# WL-FRONT.net
KiCad netlist of a schematic drawn in Altium Designer
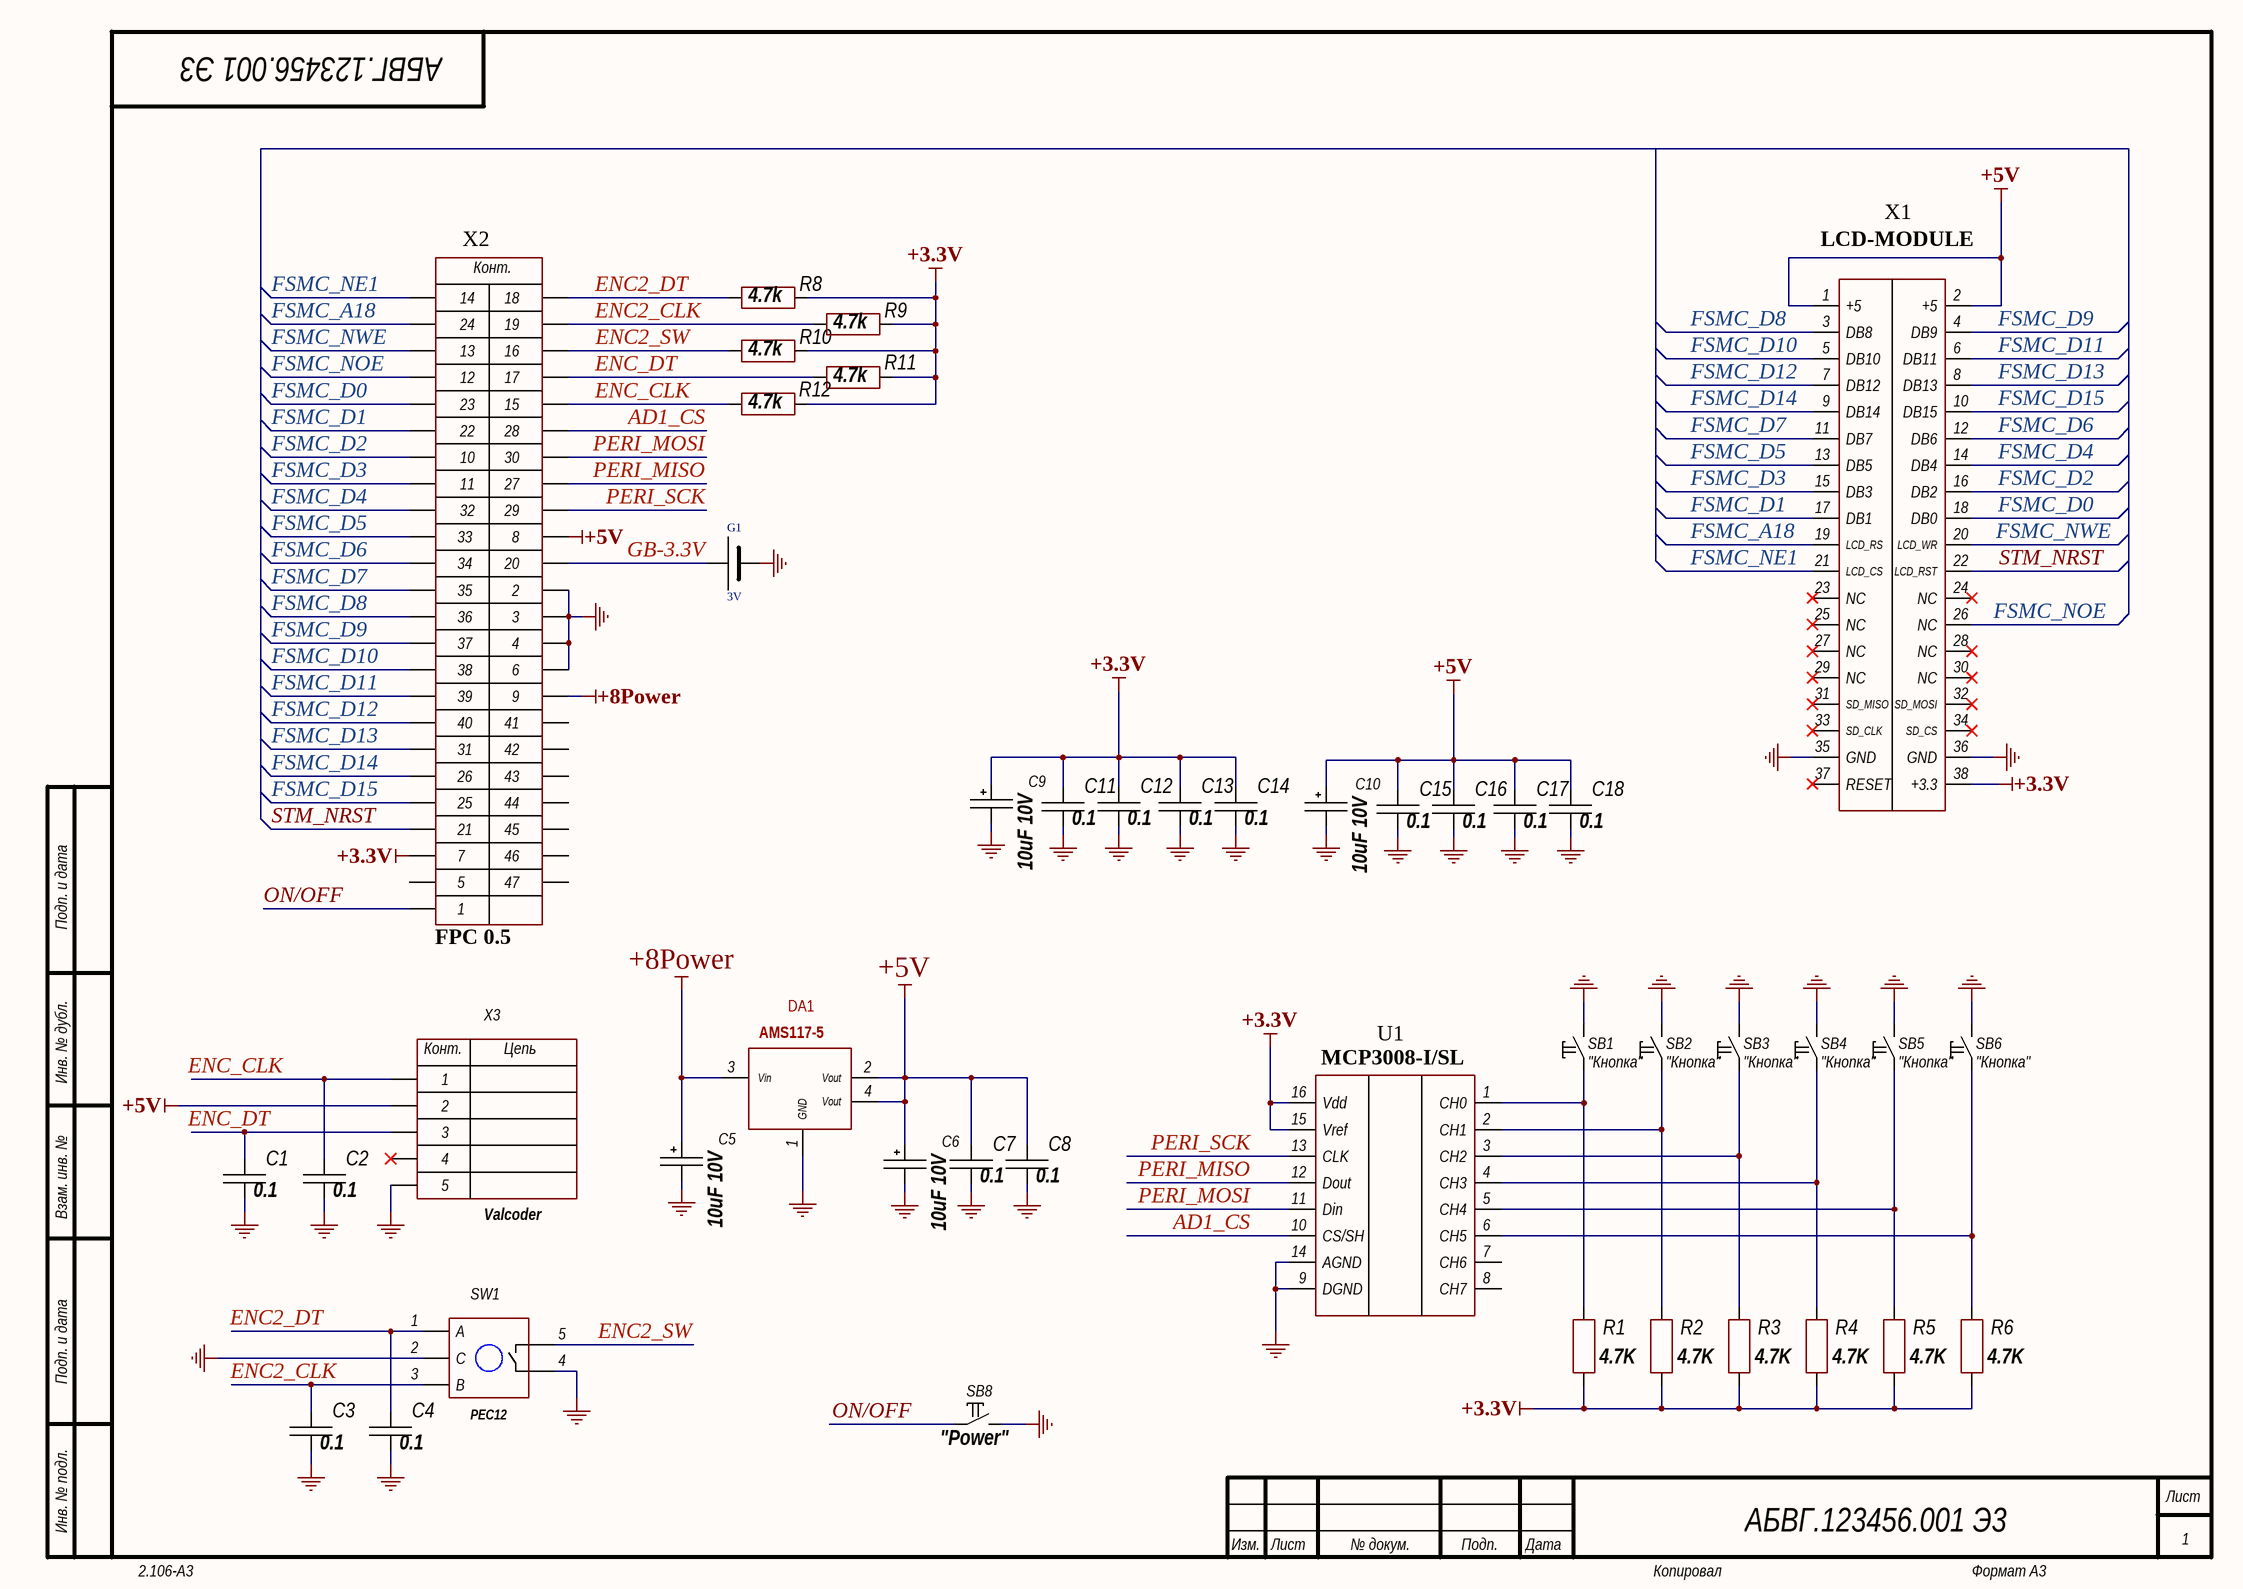
[diagram p0: WL-FRONT.SchDoc]

(export (version "E")
  (design (tool "Eeschema 10.0.6"))
  (components
    (comp (ref "C1")
      (value "0.1")
      (footprint "standard:CH0805C")
      (libsource (lib "Discrete") (part "Capacitor"))
    )
    (comp (ref "C2")
      (value "0.1")
      (footprint "standard:CH0805C")
      (libsource (lib "Discrete") (part "Capacitor"))
    )
    (comp (ref "C3")
      (value "0.1")
      (footprint "standard:CH0805C")
      (libsource (lib "Discrete") (part "Capacitor"))
    )
    (comp (ref "C4")
      (value "0.1")
      (footprint "standard:CH0805C")
      (libsource (lib "Discrete") (part "Capacitor"))
    )
    (comp (ref "C5")
      (value "10uF 10V")
      (footprint "standard:TANTAL_B")
      (libsource (lib "Discrete") (part "TantalCap"))
    )
    (comp (ref "C6")
      (value "10uF 10V")
      (footprint "standard:TANTAL_B")
      (libsource (lib "Discrete") (part "TantalCap"))
    )
    (comp (ref "C7")
      (value "0.1")
      (footprint "standard:CH0805C")
      (libsource (lib "Discrete") (part "Capacitor"))
    )
    (comp (ref "C8")
      (value "0.1")
      (footprint "standard:CH0805C")
      (libsource (lib "Discrete") (part "Capacitor"))
    )
    (comp (ref "C9")
      (value "10uF 10V")
      (footprint "standard:TANTAL_B")
      (libsource (lib "Discrete") (part "TantalCap"))
    )
    (comp (ref "C10")
      (value "10uF 10V")
      (footprint "standard:TANTAL_B")
      (libsource (lib "Discrete") (part "TantalCap"))
    )
    (comp (ref "C11")
      (value "0.1")
      (footprint "standard:CH0805C")
      (libsource (lib "Discrete") (part "Capacitor"))
    )
    (comp (ref "C12")
      (value "0.1")
      (footprint "standard:CH0805C")
      (libsource (lib "Discrete") (part "Capacitor"))
    )
    (comp (ref "C13")
      (value "0.1")
      (footprint "standard:CH0805C")
      (libsource (lib "Discrete") (part "Capacitor"))
    )
    (comp (ref "C14")
      (value "0.1")
      (footprint "standard:CH0805C")
      (libsource (lib "Discrete") (part "Capacitor"))
    )
    (comp (ref "C15")
      (value "0.1")
      (footprint "standard:CH0805C")
      (libsource (lib "Discrete") (part "Capacitor"))
    )
    (comp (ref "C16")
      (value "0.1")
      (footprint "standard:CH0805C")
      (libsource (lib "Discrete") (part "Capacitor"))
    )
    (comp (ref "C17")
      (value "0.1")
      (footprint "standard:CH0805C")
      (libsource (lib "Discrete") (part "Capacitor"))
    )
    (comp (ref "C18")
      (value "0.1")
      (footprint "standard:CH0805C")
      (libsource (lib "Discrete") (part "Capacitor"))
    )
    (comp (ref "DA1") (value "AMS117-5") (footprint "SOT223") (libsource (lib "Analog") (part "AMS117")))
    (comp (ref "G1")
      (value "3V")
      (footprint "BAT: CH224-2032")
      (libsource (lib "Connectors") (part "POWER_BAT"))
    )
    (comp (ref "R1") (value "4.7K") (footprint "standard:CH0805R") (libsource (lib "") (part "Resistor_1")))
    (comp (ref "R2") (value "4.7K") (footprint "standard:CH0805R") (libsource (lib "") (part "Resistor_1")))
    (comp (ref "R3") (value "4.7K") (footprint "standard:CH0805R") (libsource (lib "") (part "Resistor_2")))
    (comp (ref "R4") (value "4.7K") (footprint "standard:CH0805R") (libsource (lib "") (part "Resistor_1")))
    (comp (ref "R5") (value "4.7K") (footprint "standard:CH0805R") (libsource (lib "") (part "Resistor_1")))
    (comp (ref "R6") (value "4.7K") (footprint "standard:CH0805R") (libsource (lib "") (part "Resistor_1")))
    (comp (ref "R8")
      (value "4.7k")
      (footprint "standard:CH0805R")
      (libsource (lib "Discrete") (part "Resistor"))
    )
    (comp (ref "R9")
      (value "4.7k")
      (footprint "standard:CH0805R")
      (libsource (lib "Discrete") (part "Resistor"))
    )
    (comp (ref "R10")
      (value "4.7k")
      (footprint "standard:CH0805R")
      (libsource (lib "Discrete") (part "Resistor"))
    )
    (comp (ref "R11")
      (value "4.7k")
      (footprint "standard:CH0805R")
      (libsource (lib "Discrete") (part "Resistor"))
    )
    (comp (ref "R12")
      (value "4.7k")
      (footprint "standard:CH0805R")
      (libsource (lib "Discrete") (part "Resistor"))
    )
    (comp (ref "SB1")
      (value "\"Кнопка\"")
      (footprint "custom:BUT: 6x6 SMD")
      (description "6x6 mm")
      (libsource (lib "Connectors") (part "Tactile switches"))
    )
    (comp (ref "SB2")
      (value "\"Кнопка\"")
      (footprint "custom:BUT: 6x6 SMD")
      (description "6x6 mm")
      (libsource (lib "Connectors") (part "Tactile switches"))
    )
    (comp (ref "SB3")
      (value "\"Кнопка\"")
      (footprint "custom:BUT: 6x6 SMD")
      (description "6x6 mm")
      (libsource (lib "") (part "Tactile switches_1"))
    )
    (comp (ref "SB4")
      (value "\"Кнопка\"")
      (footprint "custom:BUT: 6x6 SMD")
      (description "6x6 mm")
      (libsource (lib "Connectors") (part "Tactile switches"))
    )
    (comp (ref "SB5")
      (value "\"Кнопка\"")
      (footprint "custom:BUT: 6x6 SMD")
      (description "6x6 mm")
      (libsource (lib "Connectors") (part "Tactile switches"))
    )
    (comp (ref "SB6")
      (value "\"Кнопка\"")
      (footprint "custom:BUT: 6x6 SMD")
      (description "6x6 mm")
      (libsource (lib "Connectors") (part "Tactile switches"))
    )
    (comp (ref "SB8")
      (value "\"Power\"")
      (footprint "custom:BUT: 6x6")
      (description "6x6 mm")
      (libsource (lib "Connectors") (part "Tactile switches"))
    )
    (comp (ref "SW1")
      (value "PEC12")
      (footprint "Valkoder-m2")
      (description "Encoder")
      (libsource (lib "Connectors") (part "PEC12"))
    )
    (comp (ref "U1")
      (value "MCP3008-I/SL")
      (footprint "16-SOIC")
      (libsource (lib "Digital") (part "MCP3008-I/SL"))
    )
    (comp (ref "X1")
      (value "LCD-MODULE")
      (footprint "TFT3.2-320x480-pin")
      (libsource (lib "Digital") (part "LCD-MODULE"))
    )
    (comp (ref "X2")
      (value "FPC 0.5")
      (footprint "CON: PBD2x20")
      (libsource (lib "Connectors") (part "FPC-45-0.5"))
    )
    (comp (ref "X3")
      (value "Valcoder")
      (footprint "custom:CON: PLS-5")
      (libsource (lib "Connectors") (part "5-Connector"))
    )
  )
  (nets
    (net (code "1") (name "+3.3V") (class "Default")
      (node (ref "C11") (pin "1") (pinfunction "1_1") (pintype "power_in"))
      (node (ref "C12") (pin "1") (pinfunction "1_1") (pintype "power_in"))
      (node (ref "C13") (pin "1") (pinfunction "1_1") (pintype "power_in"))
      (node (ref "C14") (pin "1") (pinfunction "1_1") (pintype "power_in"))
      (node (ref "C9") (pin "1") (pinfunction "1_1") (pintype "power_in"))
      (node (ref "R1") (pin "1") (pinfunction "1_1") (pintype "passive"))
      (node (ref "R10") (pin "1") (pinfunction "1_1") (pintype "passive"))
      (node (ref "R11") (pin "1") (pinfunction "1_1") (pintype "passive"))
      (node (ref "R12") (pin "1") (pinfunction "1_1") (pintype "passive"))
      (node (ref "R2") (pin "1") (pinfunction "1_1") (pintype "passive"))
      (node (ref "R3") (pin "1") (pinfunction "1_1") (pintype "passive"))
      (node (ref "R4") (pin "1") (pinfunction "1_1") (pintype "passive"))
      (node (ref "R5") (pin "1") (pinfunction "1_1") (pintype "passive"))
      (node (ref "R6") (pin "1") (pinfunction "1_1") (pintype "passive"))
      (node (ref "R8") (pin "1") (pinfunction "1_1") (pintype "passive"))
      (node (ref "R9") (pin "1") (pinfunction "1_1") (pintype "passive"))
      (node (ref "U1") (pin "15") (pinfunction "Vref_15") (pintype "passive"))
      (node (ref "U1") (pin "16") (pinfunction "Vdd_16") (pintype "passive"))
      (node (ref "X1") (pin "38") (pinfunction "+3.3_38") (pintype "passive"))
      (node (ref "X2") (pin "7") (pinfunction "7_7") (pintype "power_in"))
    )
    (net (code "2") (name "+5V") (class "Default")
      (node (ref "C10") (pin "1") (pinfunction "1_1") (pintype "power_in"))
      (node (ref "C15") (pin "1") (pinfunction "1_1") (pintype "power_in"))
      (node (ref "C16") (pin "1") (pinfunction "1_1") (pintype "power_in"))
      (node (ref "C17") (pin "1") (pinfunction "1_1") (pintype "power_in"))
      (node (ref "C18") (pin "1") (pinfunction "1_1") (pintype "power_in"))
      (node (ref "C6") (pin "1") (pinfunction "1_1") (pintype "power_in"))
      (node (ref "C7") (pin "1") (pinfunction "1_1") (pintype "power_in"))
      (node (ref "C8") (pin "1") (pinfunction "1_1") (pintype "power_in"))
      (node (ref "DA1") (pin "2") (pinfunction "Vout_2") (pintype "passive"))
      (node (ref "DA1") (pin "4") (pinfunction "Vout_4") (pintype "passive"))
      (node (ref "X1") (pin "1") (pinfunction "+5_1") (pintype "passive"))
      (node (ref "X1") (pin "2") (pinfunction "+5_2") (pintype "passive"))
      (node (ref "X2") (pin "8") (pinfunction "8_8") (pintype "power_in"))
      (node (ref "X3") (pin "2") (pinfunction "2_2") (pintype "passive"))
    )
    (net (code "3") (name "+8Power") (class "Default")
      (node (ref "C5") (pin "1") (pinfunction "1_1") (pintype "power_in"))
      (node (ref "DA1") (pin "3") (pinfunction "Vin_3") (pintype "passive"))
      (node (ref "X2") (pin "9") (pinfunction "9_9") (pintype "power_in"))
    )
    (net (code "4") (name "/AD1_CS") (class "Default")
      (node (ref "U1") (pin "10") (pinfunction "CS/SH_10") (pintype "passive"))
      (node (ref "X2") (pin "28") (pinfunction "28_28") (pintype "power_in"))
    )
    (net (code "5") (name "/ENC2_CLK") (class "Default")
      (node (ref "C3") (pin "1") (pinfunction "1_1") (pintype "power_in"))
      (node (ref "R9") (pin "2") (pinfunction "2_2") (pintype "passive"))
      (node (ref "SW1") (pin "3") (pinfunction "B_3") (pintype "passive"))
      (node (ref "X2") (pin "19") (pinfunction "19_19") (pintype "power_in"))
    )
    (net (code "6") (name "/ENC2_DT") (class "Default")
      (node (ref "C4") (pin "1") (pinfunction "1_1") (pintype "power_in"))
      (node (ref "R8") (pin "2") (pinfunction "2_2") (pintype "passive"))
      (node (ref "SW1") (pin "1") (pinfunction "A_1") (pintype "passive"))
      (node (ref "X2") (pin "18") (pinfunction "18_18") (pintype "power_in"))
    )
    (net (code "7") (name "/ENC2_SW") (class "Default")
      (node (ref "R10") (pin "2") (pinfunction "2_2") (pintype "passive"))
      (node (ref "SW1") (pin "5") (pinfunction "5_5") (pintype "passive"))
      (node (ref "X2") (pin "16") (pinfunction "16_16") (pintype "power_in"))
    )
    (net (code "8") (name "/ENC_CLK") (class "Default")
      (node (ref "C2") (pin "1") (pinfunction "1_1") (pintype "power_in"))
      (node (ref "R12") (pin "2") (pinfunction "2_2") (pintype "passive"))
      (node (ref "X2") (pin "15") (pinfunction "15_15") (pintype "power_in"))
      (node (ref "X3") (pin "1") (pinfunction "1_1") (pintype "passive"))
    )
    (net (code "9") (name "/ENC_DT") (class "Default")
      (node (ref "C1") (pin "1") (pinfunction "1_1") (pintype "power_in"))
      (node (ref "R11") (pin "2") (pinfunction "2_2") (pintype "passive"))
      (node (ref "X2") (pin "17") (pinfunction "17_17") (pintype "power_in"))
      (node (ref "X3") (pin "3") (pinfunction "3_3") (pintype "power_in"))
    )
    (net (code "10") (name "/FSMC_A18") (class "Default")
      (node (ref "X1") (pin "19") (pinfunction "LCD_RS_19") (pintype "passive"))
      (node (ref "X2") (pin "24") (pinfunction "24_24") (pintype "passive"))
    )
    (net (code "11") (name "/FSMC_D0") (class "Default")
      (node (ref "X1") (pin "18") (pinfunction "DB0_18") (pintype "passive"))
      (node (ref "X2") (pin "23") (pinfunction "23_23") (pintype "power_in"))
    )
    (net (code "12") (name "/FSMC_D1") (class "Default")
      (node (ref "X1") (pin "17") (pinfunction "DB1_17") (pintype "passive"))
      (node (ref "X2") (pin "22") (pinfunction "22_22") (pintype "power_in"))
    )
    (net (code "13") (name "/FSMC_D2") (class "Default")
      (node (ref "X1") (pin "16") (pinfunction "DB2_16") (pintype "passive"))
      (node (ref "X2") (pin "10") (pinfunction "10_10") (pintype "power_in"))
    )
    (net (code "14") (name "/FSMC_D3") (class "Default")
      (node (ref "X1") (pin "15") (pinfunction "DB3_15") (pintype "passive"))
      (node (ref "X2") (pin "11") (pinfunction "11_11") (pintype "power_in"))
    )
    (net (code "15") (name "/FSMC_D4") (class "Default")
      (node (ref "X1") (pin "14") (pinfunction "DB4_14") (pintype "passive"))
      (node (ref "X2") (pin "32") (pinfunction "32_32") (pintype "power_in"))
    )
    (net (code "16") (name "/FSMC_D5") (class "Default")
      (node (ref "X1") (pin "13") (pinfunction "DB5_13") (pintype "passive"))
      (node (ref "X2") (pin "33") (pinfunction "33_33") (pintype "power_in"))
    )
    (net (code "17") (name "/FSMC_D6") (class "Default")
      (node (ref "X1") (pin "12") (pinfunction "DB6_12") (pintype "passive"))
      (node (ref "X2") (pin "34") (pinfunction "34_34") (pintype "power_in"))
    )
    (net (code "18") (name "/FSMC_D7") (class "Default")
      (node (ref "X1") (pin "11") (pinfunction "DB7_11") (pintype "passive"))
      (node (ref "X2") (pin "35") (pinfunction "35_35") (pintype "power_in"))
    )
    (net (code "19") (name "/FSMC_D8") (class "Default")
      (node (ref "X1") (pin "3") (pinfunction "DB8_3") (pintype "passive"))
      (node (ref "X2") (pin "36") (pinfunction "36_36") (pintype "power_in"))
    )
    (net (code "20") (name "/FSMC_D9") (class "Default")
      (node (ref "X1") (pin "4") (pinfunction "DB9_4") (pintype "passive"))
      (node (ref "X2") (pin "37") (pinfunction "37_37") (pintype "power_in"))
    )
    (net (code "21") (name "/FSMC_D10") (class "Default")
      (node (ref "X1") (pin "5") (pinfunction "DB10_5") (pintype "passive"))
      (node (ref "X2") (pin "38") (pinfunction "38_38") (pintype "power_in"))
    )
    (net (code "22") (name "/FSMC_D11") (class "Default")
      (node (ref "X1") (pin "6") (pinfunction "DB11_6") (pintype "passive"))
      (node (ref "X2") (pin "39") (pinfunction "39_39") (pintype "power_in"))
    )
    (net (code "23") (name "/FSMC_D12") (class "Default")
      (node (ref "X1") (pin "7") (pinfunction "DB12_7") (pintype "passive"))
      (node (ref "X2") (pin "40") (pinfunction "40_40") (pintype "power_in"))
    )
    (net (code "24") (name "/FSMC_D13") (class "Default")
      (node (ref "X1") (pin "8") (pinfunction "DB13_8") (pintype "passive"))
      (node (ref "X2") (pin "31") (pinfunction "31_31") (pintype "power_in"))
    )
    (net (code "25") (name "/FSMC_D14") (class "Default")
      (node (ref "X1") (pin "9") (pinfunction "DB14_9") (pintype "passive"))
      (node (ref "X2") (pin "26") (pinfunction "26_26") (pintype "power_in"))
    )
    (net (code "26") (name "/FSMC_D15") (class "Default")
      (node (ref "X1") (pin "10") (pinfunction "DB15_10") (pintype "passive"))
      (node (ref "X2") (pin "25") (pinfunction "25_25") (pintype "power_in"))
    )
    (net (code "27") (name "/FSMC_NE1") (class "Default")
      (node (ref "X1") (pin "21") (pinfunction "LCD_CS_21") (pintype "passive"))
      (node (ref "X2") (pin "14") (pinfunction "14_14") (pintype "passive"))
    )
    (net (code "28") (name "/FSMC_NOE") (class "Default")
      (node (ref "X1") (pin "26") (pinfunction "NC_26") (pintype "passive"))
      (node (ref "X2") (pin "12") (pinfunction "12_12") (pintype "power_in"))
    )
    (net (code "29") (name "/FSMC_NWE") (class "Default")
      (node (ref "X1") (pin "20") (pinfunction "LCD_WR_20") (pintype "passive"))
      (node (ref "X2") (pin "13") (pinfunction "13_13") (pintype "power_in"))
    )
    (net (code "30") (name "/GB-3.3V") (class "Default")
      (node (ref "G1") (pin "1") (pinfunction "0_1") (pintype "passive"))
      (node (ref "X2") (pin "20") (pinfunction "20_20") (pintype "power_in"))
    )
    (net (code "31") (name "/ON{slash}OFF") (class "Default")
      (node (ref "SB8") (pin "1") (pinfunction "1_1") (pintype "passive"))
      (node (ref "X2") (pin "1") (pinfunction "1_1") (pintype "power_in"))
    )
    (net (code "32") (name "/PERI_MISO") (class "Default")
      (node (ref "U1") (pin "12") (pinfunction "Dout_12") (pintype "passive"))
      (node (ref "X2") (pin "27") (pinfunction "27_27") (pintype "power_in"))
    )
    (net (code "33") (name "/PERI_MOSI") (class "Default")
      (node (ref "U1") (pin "11") (pinfunction "Din_11") (pintype "passive"))
      (node (ref "X2") (pin "30") (pinfunction "30_30") (pintype "power_in"))
    )
    (net (code "34") (name "/PERI_SCK") (class "Default")
      (node (ref "U1") (pin "13") (pinfunction "CLK_13") (pintype "passive"))
      (node (ref "X2") (pin "29") (pinfunction "29_29") (pintype "power_in"))
    )
    (net (code "35") (name "/STM_NRST") (class "Default")
      (node (ref "X1") (pin "22") (pinfunction "LCD_RST_22") (pintype "passive"))
      (node (ref "X2") (pin "21") (pinfunction "21_21") (pintype "power_in"))
    )
    (net (code "36") (name "GND") (class "Default")
      (node (ref "C1") (pin "2") (pinfunction "2_2") (pintype "power_in"))
      (node (ref "C10") (pin "2") (pinfunction "2_2") (pintype "power_in"))
      (node (ref "C11") (pin "2") (pinfunction "2_2") (pintype "power_in"))
      (node (ref "C12") (pin "2") (pinfunction "2_2") (pintype "power_in"))
      (node (ref "C13") (pin "2") (pinfunction "2_2") (pintype "power_in"))
      (node (ref "C14") (pin "2") (pinfunction "2_2") (pintype "power_in"))
      (node (ref "C15") (pin "2") (pinfunction "2_2") (pintype "power_in"))
      (node (ref "C16") (pin "2") (pinfunction "2_2") (pintype "power_in"))
      (node (ref "C17") (pin "2") (pinfunction "2_2") (pintype "power_in"))
      (node (ref "C18") (pin "2") (pinfunction "2_2") (pintype "power_in"))
      (node (ref "C2") (pin "2") (pinfunction "2_2") (pintype "power_in"))
      (node (ref "C3") (pin "2") (pinfunction "2_2") (pintype "power_in"))
      (node (ref "C4") (pin "2") (pinfunction "2_2") (pintype "power_in"))
      (node (ref "C5") (pin "2") (pinfunction "2_2") (pintype "power_in"))
      (node (ref "C6") (pin "2") (pinfunction "2_2") (pintype "power_in"))
      (node (ref "C7") (pin "2") (pinfunction "2_2") (pintype "power_in"))
      (node (ref "C8") (pin "2") (pinfunction "2_2") (pintype "power_in"))
      (node (ref "C9") (pin "2") (pinfunction "2_2") (pintype "power_in"))
      (node (ref "DA1") (pin "1") (pinfunction "GND_1") (pintype "passive"))
      (node (ref "G1") (pin "2") (pinfunction "1_2") (pintype "passive"))
      (node (ref "SB1") (pin "2") (pinfunction "2_2") (pintype "passive"))
      (node (ref "SB2") (pin "2") (pinfunction "2_2") (pintype "passive"))
      (node (ref "SB3") (pin "2") (pinfunction "2_2") (pintype "passive"))
      (node (ref "SB4") (pin "2") (pinfunction "2_2") (pintype "passive"))
      (node (ref "SB5") (pin "2") (pinfunction "2_2") (pintype "passive"))
      (node (ref "SB6") (pin "2") (pinfunction "2_2") (pintype "passive"))
      (node (ref "SB8") (pin "2") (pinfunction "2_2") (pintype "passive"))
      (node (ref "SW1") (pin "2") (pinfunction "C_2") (pintype "passive"))
      (node (ref "SW1") (pin "4") (pinfunction "4_4") (pintype "passive"))
      (node (ref "U1") (pin "14") (pinfunction "AGND_14") (pintype "passive"))
      (node (ref "U1") (pin "9") (pinfunction "DGND_9") (pintype "passive"))
      (node (ref "X1") (pin "35") (pinfunction "GND_35") (pintype "passive"))
      (node (ref "X1") (pin "36") (pinfunction "GND_36") (pintype "passive"))
      (node (ref "X2") (pin "2") (pinfunction "2_2") (pintype "power_in"))
      (node (ref "X2") (pin "3") (pinfunction "3_3") (pintype "power_in"))
      (node (ref "X2") (pin "4") (pinfunction "4_4") (pintype "power_in"))
      (node (ref "X2") (pin "6") (pinfunction "6_6") (pintype "power_in"))
      (node (ref "X3") (pin "5") (pinfunction "5_5") (pintype "power_in"))
    )
    (net (code "37") (name "Net-(U1-CH0)") (class "Default")
      (node (ref "R1") (pin "2") (pinfunction "2_2") (pintype "passive"))
      (node (ref "SB1") (pin "1") (pinfunction "1_1") (pintype "passive"))
      (node (ref "U1") (pin "1") (pinfunction "CH0_1") (pintype "passive"))
    )
    (net (code "38") (name "Net-(U1-CH1)") (class "Default")
      (node (ref "R2") (pin "2") (pinfunction "2_2") (pintype "passive"))
      (node (ref "SB2") (pin "1") (pinfunction "1_1") (pintype "passive"))
      (node (ref "U1") (pin "2") (pinfunction "CH1_2") (pintype "passive"))
    )
    (net (code "39") (name "Net-(U1-CH2)") (class "Default")
      (node (ref "R3") (pin "2") (pinfunction "2_2") (pintype "passive"))
      (node (ref "SB3") (pin "1") (pinfunction "1_1") (pintype "passive"))
      (node (ref "U1") (pin "3") (pinfunction "CH2_3") (pintype "passive"))
    )
    (net (code "40") (name "Net-(U1-CH3)") (class "Default")
      (node (ref "R4") (pin "2") (pinfunction "2_2") (pintype "passive"))
      (node (ref "SB4") (pin "1") (pinfunction "1_1") (pintype "passive"))
      (node (ref "U1") (pin "4") (pinfunction "CH3_4") (pintype "passive"))
    )
    (net (code "41") (name "Net-(U1-CH4)") (class "Default")
      (node (ref "R5") (pin "2") (pinfunction "2_2") (pintype "passive"))
      (node (ref "SB5") (pin "1") (pinfunction "1_1") (pintype "passive"))
      (node (ref "U1") (pin "5") (pinfunction "CH4_5") (pintype "passive"))
    )
    (net (code "42") (name "Net-(U1-CH5)") (class "Default")
      (node (ref "R6") (pin "2") (pinfunction "2_2") (pintype "passive"))
      (node (ref "SB6") (pin "1") (pinfunction "1_1") (pintype "passive"))
      (node (ref "U1") (pin "6") (pinfunction "CH5_6") (pintype "passive"))
    )
    (net (code "43") (name "unconnected-(U1-CH6-Pad7)") (class "Default")
      (node (ref "U1") (pin "7") (pinfunction "CH6_7") (pintype "passive"))
    )
    (net (code "44") (name "unconnected-(U1-CH7-Pad8)") (class "Default")
      (node (ref "U1") (pin "8") (pinfunction "CH7_8") (pintype "passive"))
    )
    (net (code "45") (name "unconnected-(X1-NC-Pad23)") (class "Default")
      (node (ref "X1") (pin "23") (pinfunction "NC_23") (pintype "passive+no_connect"))
    )
    (net (code "46") (name "unconnected-(X1-NC-Pad24)") (class "Default")
      (node (ref "X1") (pin "24") (pinfunction "NC_24") (pintype "passive+no_connect"))
    )
    (net (code "47") (name "unconnected-(X1-NC-Pad25)") (class "Default")
      (node (ref "X1") (pin "25") (pinfunction "NC_25") (pintype "passive+no_connect"))
    )
    (net (code "48") (name "unconnected-(X1-NC-Pad27)") (class "Default")
      (node (ref "X1") (pin "27") (pinfunction "NC_27") (pintype "passive+no_connect"))
    )
    (net (code "49") (name "unconnected-(X1-NC-Pad28)") (class "Default")
      (node (ref "X1") (pin "28") (pinfunction "NC_28") (pintype "passive+no_connect"))
    )
    (net (code "50") (name "unconnected-(X1-NC-Pad29)") (class "Default")
      (node (ref "X1") (pin "29") (pinfunction "NC_29") (pintype "passive+no_connect"))
    )
    (net (code "51") (name "unconnected-(X1-NC-Pad30)") (class "Default")
      (node (ref "X1") (pin "30") (pinfunction "NC_30") (pintype "passive+no_connect"))
    )
    (net (code "52") (name "unconnected-(X1-RESET-Pad37)") (class "Default")
      (node (ref "X1") (pin "37") (pinfunction "RESET_37") (pintype "passive+no_connect"))
    )
    (net (code "53") (name "unconnected-(X1-SD_CLK-Pad33)") (class "Default")
      (node (ref "X1") (pin "33") (pinfunction "SD_CLK_33") (pintype "passive+no_connect"))
    )
    (net (code "54") (name "unconnected-(X1-SD_CS-Pad34)") (class "Default")
      (node (ref "X1") (pin "34") (pinfunction "SD_CS_34") (pintype "passive+no_connect"))
    )
    (net (code "55") (name "unconnected-(X1-SD_MISO-Pad31)") (class "Default")
      (node (ref "X1") (pin "31") (pinfunction "SD_MISO_31") (pintype "passive+no_connect"))
    )
    (net (code "56") (name "unconnected-(X1-SD_MOSI-Pad32)") (class "Default")
      (node (ref "X1") (pin "32") (pinfunction "SD_MOSI_32") (pintype "passive+no_connect"))
    )
    (net (code "57") (name "unconnected-(X2-Pad5)") (class "Default")
      (node (ref "X2") (pin "5") (pinfunction "5_5") (pintype "power_in"))
    )
    (net (code "58") (name "unconnected-(X2-Pad41)") (class "Default")
      (node (ref "X2") (pin "41") (pinfunction "41_41") (pintype "power_in"))
    )
    (net (code "59") (name "unconnected-(X2-Pad42)") (class "Default")
      (node (ref "X2") (pin "42") (pinfunction "42_42") (pintype "power_in"))
    )
    (net (code "60") (name "unconnected-(X2-Pad43)") (class "Default")
      (node (ref "X2") (pin "43") (pinfunction "43_43") (pintype "power_in"))
    )
    (net (code "61") (name "unconnected-(X2-Pad44)") (class "Default")
      (node (ref "X2") (pin "44") (pinfunction "44_44") (pintype "power_in"))
    )
    (net (code "62") (name "unconnected-(X2-Pad45)") (class "Default")
      (node (ref "X2") (pin "45") (pinfunction "45_45") (pintype "power_in"))
    )
    (net (code "63") (name "unconnected-(X2-Pad46)") (class "Default")
      (node (ref "X2") (pin "46") (pinfunction "46_46") (pintype "power_in"))
    )
    (net (code "64") (name "unconnected-(X2-Pad47)") (class "Default")
      (node (ref "X2") (pin "47") (pinfunction "47_47") (pintype "power_in"))
    )
    (net (code "65") (name "unconnected-(X3-Pad4)") (class "Default")
      (node (ref "X3") (pin "4") (pinfunction "4_4") (pintype "power_in+no_connect"))
    )
  )
)
